# godmd_V1_final.net
KiCad netlist of a schematic drawn in EAGLE
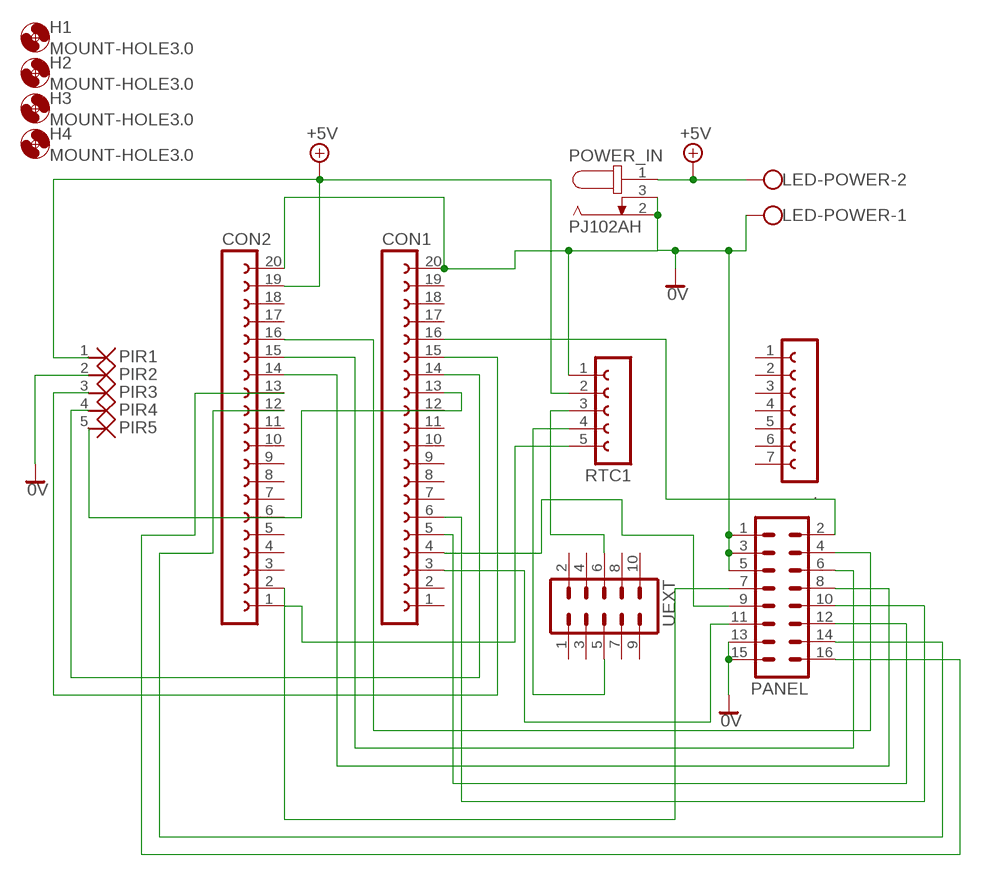
[diagram p0: schematic, sheet 1]

(export (version "E")
  (design (tool "Eeschema 10.0.6"))
  (components
    (comp (ref ".")
      (value "FE07-1")
      (footprint "eagle-import:FE07")
      (libsource (lib "eagle-import") (part "FE07-1"))
    )
    (comp (ref "CON1")
      (value "FE20-1")
      (footprint "eagle-import:FE20")
      (libsource (lib "eagle-import") (part "FE20-1"))
    )
    (comp (ref "CON2")
      (value "FE20-1")
      (footprint "eagle-import:FE20")
      (libsource (lib "eagle-import") (part "FE20-1"))
    )
    (comp (ref "H1")
      (value "MOUNT-HOLE3.0")
      (footprint "eagle-import:3,0")
      (libsource (lib "eagle-import") (part "MOUNT-HOLE3.0"))
    )
    (comp (ref "H2")
      (value "MOUNT-HOLE3.0")
      (footprint "eagle-import:3,0")
      (libsource (lib "eagle-import") (part "MOUNT-HOLE3.0"))
    )
    (comp (ref "H3")
      (value "MOUNT-HOLE3.0")
      (footprint "eagle-import:3,0")
      (libsource (lib "eagle-import") (part "MOUNT-HOLE3.0"))
    )
    (comp (ref "H4")
      (value "MOUNT-HOLE3.0")
      (footprint "eagle-import:3,0")
      (libsource (lib "eagle-import") (part "MOUNT-HOLE3.0"))
    )
    (comp (ref "LED-POWER")
      (value "W237-102")
      (footprint "eagle-import:W237-102")
      (fields (field (name "MPN") "237-102"))
      (libsource (lib "eagle-import") (part "W237-102"))
    )
    (comp (ref "PANEL")
      (value "MA08-2")
      (footprint "eagle-import:MA08-2")
      (libsource (lib "eagle-import") (part "MA08-2"))
    )
    (comp (ref "PIR")
      (value "PS25_5")
      (footprint "eagle-import:PS25_5")
      (libsource (lib "eagle-import") (part "PS25_5"))
    )
    (comp (ref "POWER_IN")
      (value "PJ102AH")
      (footprint "eagle-import:PJ102")
      (libsource (lib "eagle-import") (part "PJ102AH"))
    )
    (comp (ref "RTC1")
      (value "FE05-1")
      (footprint "eagle-import:FE05-1")
      (libsource (lib "eagle-import") (part "FE05-1"))
    )
    (comp (ref "UEXT")
      (value "ML10")
      (footprint "eagle-import:ML10")
      (libsource (lib "eagle-import") (part "ML10"))
    )
  )
  (nets
    (net (code "1") (name "+5V") (class "Default")
      (node (ref "CON2") (pin "19") (pinfunction "19_19") (pintype "passive"))
      (node (ref "LED-POWER") (pin "2") (pinfunction "KL_2") (pintype "passive"))
      (node (ref "PIR") (pin "1") (pinfunction "P$1_1") (pintype "passive"))
      (node (ref "POWER_IN") (pin "1") (pinfunction "3_1") (pintype "passive"))
      (node (ref "RTC1") (pin "2") (pinfunction "2_2") (pintype "passive"))
    )
    (net (code "2") (name "0V") (class "Default")
      (node (ref "CON1") (pin "20") (pinfunction "20_20") (pintype "passive"))
      (node (ref "CON2") (pin "20") (pinfunction "20_20") (pintype "passive"))
      (node (ref "LED-POWER") (pin "1") (pinfunction "KL_1") (pintype "passive"))
      (node (ref "PANEL") (pin "1") (pinfunction "1_1") (pintype "passive"))
      (node (ref "PANEL") (pin "13") (pinfunction "13_13") (pintype "passive"))
      (node (ref "PANEL") (pin "15") (pinfunction "15_15") (pintype "passive"))
      (node (ref "PANEL") (pin "3") (pinfunction "3_3") (pintype "passive"))
      (node (ref "PANEL") (pin "5") (pinfunction "5_5") (pintype "passive"))
      (node (ref "PIR") (pin "2") (pinfunction "P$1_2") (pintype "passive"))
      (node (ref "POWER_IN") (pin "2") (pinfunction "1_2") (pintype "passive"))
      (node (ref "POWER_IN") (pin "3") (pinfunction "2_3") (pintype "passive"))
      (node (ref "RTC1") (pin "1") (pinfunction "1_1") (pintype "passive"))
    )
    (net (code "3") (name "Net-(CON1-Pad3)") (class "Default")
      (node (ref "CON1") (pin "3") (pinfunction "3_3") (pintype "passive"))
      (node (ref "PANEL") (pin "11") (pinfunction "11_11") (pintype "passive"))
    )
    (net (code "4") (name "Net-(CON1-Pad4)") (class "Default")
      (node (ref "CON1") (pin "4") (pinfunction "4_4") (pintype "passive"))
      (node (ref "PANEL") (pin "9") (pinfunction "9_9") (pintype "passive"))
    )
    (net (code "5") (name "Net-(CON1-Pad5)") (class "Default")
      (node (ref "CON1") (pin "5") (pinfunction "5_5") (pintype "passive"))
      (node (ref "PANEL") (pin "12") (pinfunction "12_12") (pintype "passive"))
    )
    (net (code "6") (name "Net-(CON1-Pad6)") (class "Default")
      (node (ref "CON1") (pin "6") (pinfunction "6_6") (pintype "passive"))
      (node (ref "PANEL") (pin "10") (pinfunction "10_10") (pintype "passive"))
    )
    (net (code "7") (name "Net-(CON1-Pad16)") (class "Default")
      (node (ref "CON1") (pin "16") (pinfunction "16_16") (pintype "passive"))
      (node (ref "PANEL") (pin "2") (pinfunction "2_2") (pintype "passive"))
    )
    (net (code "8") (name "Net-(CON2-Pad1)") (class "Default")
      (node (ref "CON2") (pin "1") (pinfunction "1_1") (pintype "passive"))
      (node (ref "RTC1") (pin "5") (pinfunction "5_5") (pintype "passive"))
    )
    (net (code "9") (name "Net-(CON2-Pad2)") (class "Default")
      (node (ref "CON2") (pin "2") (pinfunction "2_2") (pintype "passive"))
      (node (ref "PANEL") (pin "7") (pinfunction "7_7") (pintype "passive"))
    )
    (net (code "10") (name "Net-(CON2-Pad12)") (class "Default")
      (node (ref "CON2") (pin "12") (pinfunction "12_12") (pintype "passive"))
      (node (ref "PANEL") (pin "14") (pinfunction "14_14") (pintype "passive"))
    )
    (net (code "11") (name "Net-(CON2-Pad13)") (class "Default")
      (node (ref "CON2") (pin "13") (pinfunction "13_13") (pintype "passive"))
      (node (ref "PANEL") (pin "16") (pinfunction "16_16") (pintype "passive"))
    )
    (net (code "12") (name "Net-(CON2-Pad14)") (class "Default")
      (node (ref "CON2") (pin "14") (pinfunction "14_14") (pintype "passive"))
      (node (ref "PANEL") (pin "8") (pinfunction "8_8") (pintype "passive"))
    )
    (net (code "13") (name "Net-(CON2-Pad15)") (class "Default")
      (node (ref "CON2") (pin "15") (pinfunction "15_15") (pintype "passive"))
      (node (ref "PANEL") (pin "6") (pinfunction "6_6") (pintype "passive"))
    )
    (net (code "14") (name "Net-(CON2-Pad16)") (class "Default")
      (node (ref "CON2") (pin "16") (pinfunction "16_16") (pintype "passive"))
      (node (ref "PANEL") (pin "4") (pinfunction "4_4") (pintype "passive"))
    )
    (net (code "15") (name "Net-(PIRC-P$1)") (class "Default")
      (node (ref "CON1") (pin "15") (pinfunction "15_15") (pintype "passive"))
      (node (ref "PIR") (pin "3") (pinfunction "P$1_3") (pintype "passive"))
    )
    (net (code "16") (name "Net-(PIRD-P$1)") (class "Default")
      (node (ref "CON1") (pin "14") (pinfunction "14_14") (pintype "passive"))
      (node (ref "PIR") (pin "4") (pinfunction "P$1_4") (pintype "passive"))
    )
    (net (code "17") (name "Net-(PIRE-P$1)") (class "Default")
      (node (ref "CON1") (pin "13") (pinfunction "13_13") (pintype "passive"))
      (node (ref "PIR") (pin "5") (pinfunction "P$1_5") (pintype "passive"))
    )
    (net (code "18") (name "Net-(RTC1-Pad3)") (class "Default")
      (node (ref "RTC1") (pin "3") (pinfunction "3_3") (pintype "passive"))
      (node (ref "UEXT") (pin "6") (pinfunction "6_6") (pintype "passive"))
    )
    (net (code "19") (name "Net-(RTC1-Pad4)") (class "Default")
      (node (ref "RTC1") (pin "4") (pinfunction "4_4") (pintype "passive"))
      (node (ref "UEXT") (pin "5") (pinfunction "5_5") (pintype "passive"))
    )
    (net (code "20") (name "unconnected-(.-Pad1)") (class "Default")
      (node (ref ".") (pin "1") (pinfunction "1_1") (pintype "passive"))
    )
    (net (code "21") (name "unconnected-(.-Pad2)") (class "Default")
      (node (ref ".") (pin "2") (pinfunction "2_2") (pintype "passive"))
    )
    (net (code "22") (name "unconnected-(.-Pad3)") (class "Default")
      (node (ref ".") (pin "3") (pinfunction "3_3") (pintype "passive"))
    )
    (net (code "23") (name "unconnected-(.-Pad4)") (class "Default")
      (node (ref ".") (pin "4") (pinfunction "4_4") (pintype "passive"))
    )
    (net (code "24") (name "unconnected-(.-Pad5)") (class "Default")
      (node (ref ".") (pin "5") (pinfunction "5_5") (pintype "passive"))
    )
    (net (code "25") (name "unconnected-(.-Pad6)") (class "Default")
      (node (ref ".") (pin "6") (pinfunction "6_6") (pintype "passive"))
    )
    (net (code "26") (name "unconnected-(.-Pad7)") (class "Default")
      (node (ref ".") (pin "7") (pinfunction "7_7") (pintype "passive"))
    )
    (net (code "27") (name "unconnected-(CON1-Pad1)") (class "Default")
      (node (ref "CON1") (pin "1") (pinfunction "1_1") (pintype "passive"))
    )
    (net (code "28") (name "unconnected-(CON1-Pad2)") (class "Default")
      (node (ref "CON1") (pin "2") (pinfunction "2_2") (pintype "passive"))
    )
    (net (code "29") (name "unconnected-(CON1-Pad7)") (class "Default")
      (node (ref "CON1") (pin "7") (pinfunction "7_7") (pintype "passive"))
    )
    (net (code "30") (name "unconnected-(CON1-Pad8)") (class "Default")
      (node (ref "CON1") (pin "8") (pinfunction "8_8") (pintype "passive"))
    )
    (net (code "31") (name "unconnected-(CON1-Pad9)") (class "Default")
      (node (ref "CON1") (pin "9") (pinfunction "9_9") (pintype "passive"))
    )
    (net (code "32") (name "unconnected-(CON1-Pad10)") (class "Default")
      (node (ref "CON1") (pin "10") (pinfunction "10_10") (pintype "passive"))
    )
    (net (code "33") (name "unconnected-(CON1-Pad11)") (class "Default")
      (node (ref "CON1") (pin "11") (pinfunction "11_11") (pintype "passive"))
    )
    (net (code "34") (name "unconnected-(CON1-Pad12)") (class "Default")
      (node (ref "CON1") (pin "12") (pinfunction "12_12") (pintype "passive"))
    )
    (net (code "35") (name "unconnected-(CON1-Pad17)") (class "Default")
      (node (ref "CON1") (pin "17") (pinfunction "17_17") (pintype "passive"))
    )
    (net (code "36") (name "unconnected-(CON1-Pad18)") (class "Default")
      (node (ref "CON1") (pin "18") (pinfunction "18_18") (pintype "passive"))
    )
    (net (code "37") (name "unconnected-(CON1-Pad19)") (class "Default")
      (node (ref "CON1") (pin "19") (pinfunction "19_19") (pintype "passive"))
    )
    (net (code "38") (name "unconnected-(CON2-Pad3)") (class "Default")
      (node (ref "CON2") (pin "3") (pinfunction "3_3") (pintype "passive"))
    )
    (net (code "39") (name "unconnected-(CON2-Pad4)") (class "Default")
      (node (ref "CON2") (pin "4") (pinfunction "4_4") (pintype "passive"))
    )
    (net (code "40") (name "unconnected-(CON2-Pad5)") (class "Default")
      (node (ref "CON2") (pin "5") (pinfunction "5_5") (pintype "passive"))
    )
    (net (code "41") (name "unconnected-(CON2-Pad6)") (class "Default")
      (node (ref "CON2") (pin "6") (pinfunction "6_6") (pintype "passive"))
    )
    (net (code "42") (name "unconnected-(CON2-Pad7)") (class "Default")
      (node (ref "CON2") (pin "7") (pinfunction "7_7") (pintype "passive"))
    )
    (net (code "43") (name "unconnected-(CON2-Pad8)") (class "Default")
      (node (ref "CON2") (pin "8") (pinfunction "8_8") (pintype "passive"))
    )
    (net (code "44") (name "unconnected-(CON2-Pad9)") (class "Default")
      (node (ref "CON2") (pin "9") (pinfunction "9_9") (pintype "passive"))
    )
    (net (code "45") (name "unconnected-(CON2-Pad10)") (class "Default")
      (node (ref "CON2") (pin "10") (pinfunction "10_10") (pintype "passive"))
    )
    (net (code "46") (name "unconnected-(CON2-Pad11)") (class "Default")
      (node (ref "CON2") (pin "11") (pinfunction "11_11") (pintype "passive"))
    )
    (net (code "47") (name "unconnected-(CON2-Pad17)") (class "Default")
      (node (ref "CON2") (pin "17") (pinfunction "17_17") (pintype "passive"))
    )
    (net (code "48") (name "unconnected-(CON2-Pad18)") (class "Default")
      (node (ref "CON2") (pin "18") (pinfunction "18_18") (pintype "passive"))
    )
    (net (code "49") (name "unconnected-(UEXT-Pad1)") (class "Default")
      (node (ref "UEXT") (pin "1") (pinfunction "1_1") (pintype "passive"))
    )
    (net (code "50") (name "unconnected-(UEXT-Pad2)") (class "Default")
      (node (ref "UEXT") (pin "2") (pinfunction "2_2") (pintype "passive"))
    )
    (net (code "51") (name "unconnected-(UEXT-Pad3)") (class "Default")
      (node (ref "UEXT") (pin "3") (pinfunction "3_3") (pintype "passive"))
    )
    (net (code "52") (name "unconnected-(UEXT-Pad4)") (class "Default")
      (node (ref "UEXT") (pin "4") (pinfunction "4_4") (pintype "passive"))
    )
    (net (code "53") (name "unconnected-(UEXT-Pad7)") (class "Default")
      (node (ref "UEXT") (pin "7") (pinfunction "7_7") (pintype "passive"))
    )
    (net (code "54") (name "unconnected-(UEXT-Pad8)") (class "Default")
      (node (ref "UEXT") (pin "8") (pinfunction "8_8") (pintype "passive"))
    )
    (net (code "55") (name "unconnected-(UEXT-Pad9)") (class "Default")
      (node (ref "UEXT") (pin "9") (pinfunction "9_9") (pintype "passive"))
    )
    (net (code "56") (name "unconnected-(UEXT-Pad10)") (class "Default")
      (node (ref "UEXT") (pin "10") (pinfunction "10_10") (pintype "passive"))
    )
  )
)
